# HB-power_v1_3.net
KiCad netlist of a schematic drawn in EAGLE
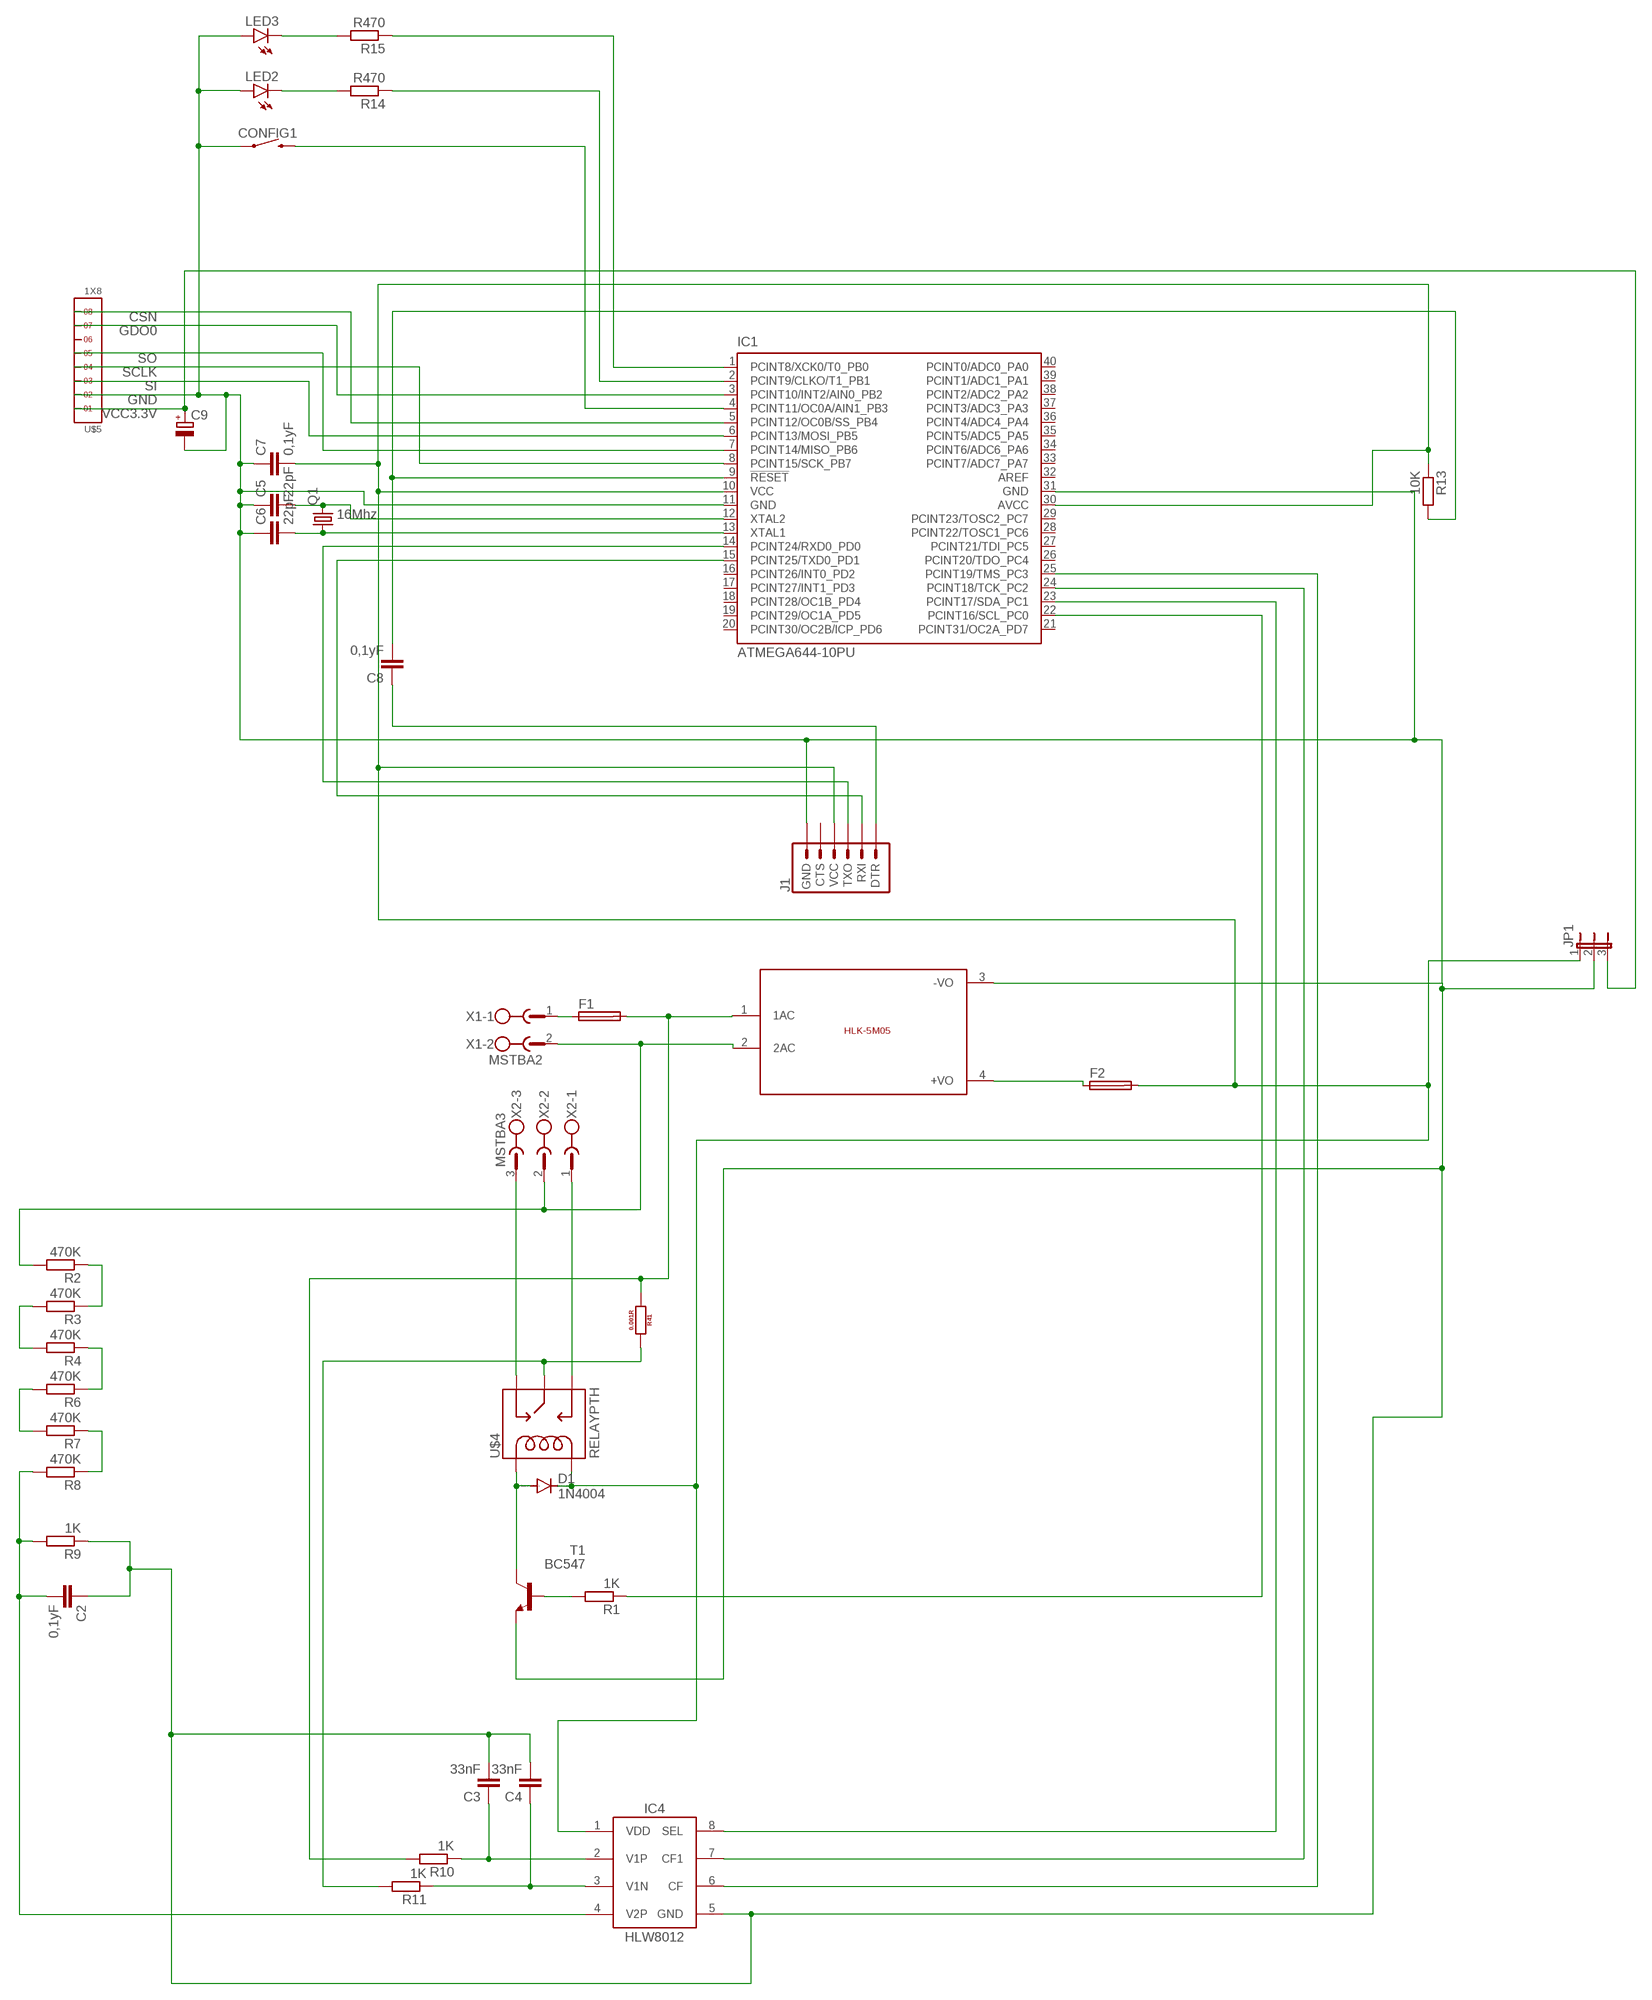
[diagram p0: schematic, sheet 1]

(export (version "E")
  (design (tool "Eeschema 10.0.6"))
  (components
    (comp (ref "C2")
      (value "0,1yF")
      (footprint "eagle-import:C050-024X044")
      (libsource (lib "eagle-import") (part "C-EU050-024X044"))
    )
    (comp (ref "C3")
      (value "33nF")
      (footprint "eagle-import:C050-024X044")
      (libsource (lib "eagle-import") (part "C-EU050-024X044"))
    )
    (comp (ref "C4")
      (value "33nF")
      (footprint "eagle-import:C050-024X044")
      (libsource (lib "eagle-import") (part "C-EU050-024X044"))
    )
    (comp (ref "C5")
      (value "22pF")
      (footprint "eagle-import:C025-024X044")
      (libsource (lib "eagle-import") (part "C-EU025-024X044"))
    )
    (comp (ref "C6")
      (value "22pF")
      (footprint "eagle-import:C025-024X044")
      (libsource (lib "eagle-import") (part "C-EU025-024X044"))
    )
    (comp (ref "C7")
      (value "0,1yF")
      (footprint "eagle-import:C025-024X044")
      (libsource (lib "eagle-import") (part "C-EU025-024X044"))
    )
    (comp (ref "C8")
      (value "0,1yF")
      (footprint "eagle-import:C025-024X044")
      (libsource (lib "eagle-import") (part "C-EU025-024X044"))
    )
    (comp (ref "C9")
      (value "CPOL-EUE2.5-5")
      (footprint "eagle-import:E2,5-5")
      (libsource (lib "eagle-import") (part "CPOL-EUE2.5-5"))
    )
    (comp (ref "CONFIG1")
      (value "MOMENTARY-SWITCH-SPST-PTH-6.0MM-KIT")
      (footprint "eagle-import:TACTILE_SWITCH_PTH_6.0MM_KIT")
      (libsource (lib "eagle-import") (part "MOMENTARY-SWITCH-SPST-PTH-6.0MM-KIT"))
    )
    (comp (ref "D1")
      (value "1N4004")
      (footprint "eagle-import:DO41-10")
      (libsource (lib "eagle-import") (part "1N4004"))
    )
    (comp (ref "F1")
      (value "SH22,5A")
      (footprint "eagle-import:SH22,5A")
      (fields (field (name "MPN") "0031.7701.11"))
      (libsource (lib "eagle-import") (part "SH22,5A"))
    )
    (comp (ref "F2")
      (value "SH22,5A")
      (footprint "eagle-import:SH22,5A")
      (fields (field (name "MPN") "0031.7701.11"))
      (libsource (lib "eagle-import") (part "SH22,5A"))
    )
    (comp (ref "IC1")
      (value "ATMEGA644-10PU")
      (footprint "eagle-import:DIL40")
      (fields (field (name "MPN") "ATMEGA644V-10PU"))
      (libsource (lib "eagle-import") (part "ATMEGA644-PU10"))
    )
    (comp (ref "IC4")
      (value "HLW8012")
      (footprint "eagle-import:SOP8")
      (libsource (lib "eagle-import") (part "HLW8012"))
    )
    (comp (ref "J1")
      (value "6_PIN_SERIAL_TARGETLONGPADS")
      (footprint "eagle-import:1X06_LONGPADS")
      (libsource (lib "eagle-import") (part "6_PIN_SERIAL_TARGETLONGPADS"))
    )
    (comp (ref "JP1")
      (value "JP2E")
      (footprint "eagle-import:JP2")
      (libsource (lib "eagle-import") (part "JP2E"))
    )
    (comp (ref "LED2")
      (value "LED3MM")
      (footprint "eagle-import:LED3MM")
      (libsource (lib "eagle-import") (part "LED3MM"))
    )
    (comp (ref "LED3")
      (value "LED3MM")
      (footprint "eagle-import:LED3MM")
      (libsource (lib "eagle-import") (part "LED3MM"))
    )
    (comp (ref "Q1")
      (value "16Mhz")
      (footprint "eagle-import:HC49U-V")
      (libsource (lib "eagle-import") (part "CRYSTALHC49U-V"))
    )
    (comp (ref "R1")
      (value "1K")
      (footprint "eagle-import:0309_10")
      (libsource (lib "eagle-import") (part "R-EU_0309/10"))
    )
    (comp (ref "R2")
      (value "470K")
      (footprint "eagle-import:0309_10")
      (libsource (lib "eagle-import") (part "R-EU_0309/10"))
    )
    (comp (ref "R3")
      (value "470K")
      (footprint "eagle-import:0309_10")
      (libsource (lib "eagle-import") (part "R-EU_0309/10"))
    )
    (comp (ref "R4")
      (value "470K")
      (footprint "eagle-import:0309_10")
      (libsource (lib "eagle-import") (part "R-EU_0309/10"))
    )
    (comp (ref "R6")
      (value "470K")
      (footprint "eagle-import:0309_10")
      (libsource (lib "eagle-import") (part "R-EU_0309/10"))
    )
    (comp (ref "R7")
      (value "470K")
      (footprint "eagle-import:0309_10")
      (libsource (lib "eagle-import") (part "R-EU_0309/10"))
    )
    (comp (ref "R8")
      (value "470K")
      (footprint "eagle-import:0309_10")
      (libsource (lib "eagle-import") (part "R-EU_0309/10"))
    )
    (comp (ref "R9")
      (value "1K")
      (footprint "eagle-import:0309_10")
      (libsource (lib "eagle-import") (part "R-EU_0309/10"))
    )
    (comp (ref "R10")
      (value "1K")
      (footprint "eagle-import:0309_10")
      (libsource (lib "eagle-import") (part "R-EU_0309/10"))
    )
    (comp (ref "R11")
      (value "1K")
      (footprint "eagle-import:0309_10")
      (libsource (lib "eagle-import") (part "R-EU_0309/10"))
    )
    (comp (ref "R13")
      (value "10K")
      (footprint "eagle-import:0309_10")
      (libsource (lib "eagle-import") (part "R-EU_0309/10"))
    )
    (comp (ref "R14")
      (value "R470")
      (footprint "eagle-import:0309_10")
      (libsource (lib "eagle-import") (part "R-EU_0309/10"))
    )
    (comp (ref "R15")
      (value "R470")
      (footprint "eagle-import:0309_10")
      (libsource (lib "eagle-import") (part "R-EU_0309/10"))
    )
    (comp (ref "R41")
      (value "0.001R")
      (footprint "eagle-import:2512")
      (libsource (lib "eagle-import") (part "RESISTOR2512"))
    )
    (comp (ref "T1")
      (value "BC547")
      (footprint "eagle-import:TO92")
      (libsource (lib "eagle-import") (part "BC547"))
    )
    (comp (ref "U$3")
      (value "5VDC/5W")
      (footprint "eagle-import:HLK-5M05")
      (libsource (lib "eagle-import") (part "HLK-5M05"))
    )
    (comp (ref "U$4")
      (value "RELAYPTH")
      (footprint "eagle-import:SRD-05VDC-SL-C")
      (libsource (lib "eagle-import") (part "RELAYPTH"))
    )
    (comp (ref "U$5")
      (value "1X8")
      (footprint "eagle-import:1X8")
      (libsource (lib "eagle-import") (part "1X8"))
    )
    (comp (ref "X1")
      (value "MSTBA2")
      (footprint "eagle-import:MSTBA2")
      (fields (field (name "MF") "FARNELL") (field (name "MPN") "1757242"))
      (libsource (lib "eagle-import") (part "MSTBA2"))
    )
    (comp (ref "X2")
      (value "MSTBA3")
      (footprint "eagle-import:MSTBA3")
      (fields (field (name "MF") "FARNELL") (field (name "MPN") "1757255"))
      (libsource (lib "eagle-import") (part "MSTBA3"))
    )
  )
  (nets
    (net (code "1") (name "/CSN") (class "Default")
      (node (ref "IC1") (pin "5") (pinfunction "PCINT12/OC0B/SS_PB4_5") (pintype "bidirectional"))
      (node (ref "U$5") (pin "8") (pinfunction "8_8") (pintype "bidirectional"))
    )
    (net (code "2") (name "/GDO0") (class "Default")
      (node (ref "IC1") (pin "3") (pinfunction "PCINT10/INT2/AIN0_PB2_3") (pintype "bidirectional"))
      (node (ref "U$5") (pin "7") (pinfunction "7_7") (pintype "bidirectional"))
    )
    (net (code "3") (name "/GND") (class "Default")
      (node (ref "C2") (pin "1") (pinfunction "1_1") (pintype "passive"))
      (node (ref "C3") (pin "2") (pinfunction "2_2") (pintype "passive"))
      (node (ref "C4") (pin "2") (pinfunction "2_2") (pintype "passive"))
      (node (ref "C5") (pin "1") (pinfunction "1_1") (pintype "passive"))
      (node (ref "C6") (pin "1") (pinfunction "1_1") (pintype "passive"))
      (node (ref "C7") (pin "1") (pinfunction "1_1") (pintype "passive"))
      (node (ref "C9") (pin "-") (pinfunction "-_-") (pintype "passive"))
      (node (ref "CONFIG1") (pin "1") (pinfunction "1_1") (pintype "passive"))
      (node (ref "IC1") (pin "11") (pinfunction "GND_11") (pintype "power_in"))
      (node (ref "IC1") (pin "31") (pinfunction "GND_31") (pintype "power_in"))
      (node (ref "IC4") (pin "5") (pinfunction "GND_5") (pintype "power_in"))
      (node (ref "J1") (pin "6") (pinfunction "GND_6") (pintype "passive"))
      (node (ref "JP1") (pin "2") (pinfunction "2_2") (pintype "passive"))
      (node (ref "LED2") (pin "A") (pinfunction "A_A") (pintype "passive"))
      (node (ref "LED3") (pin "A") (pinfunction "A_A") (pintype "passive"))
      (node (ref "R9") (pin "1") (pinfunction "1_1") (pintype "passive"))
      (node (ref "T1") (pin "1") (pinfunction "E_1") (pintype "passive"))
      (node (ref "U$3") (pin "3") (pinfunction "-VO_3") (pintype "bidirectional"))
      (node (ref "U$5") (pin "2") (pinfunction "2_2") (pintype "bidirectional"))
    )
    (net (code "4") (name "/SCLK") (class "Default")
      (node (ref "IC1") (pin "8") (pinfunction "PCINT15/SCK_PB7_8") (pintype "bidirectional"))
      (node (ref "U$5") (pin "4") (pinfunction "4_4") (pintype "bidirectional"))
    )
    (net (code "5") (name "/SI") (class "Default")
      (node (ref "IC1") (pin "6") (pinfunction "PCINT13/MOSI_PB5_6") (pintype "bidirectional"))
      (node (ref "U$5") (pin "3") (pinfunction "3_3") (pintype "bidirectional"))
    )
    (net (code "6") (name "/SO") (class "Default")
      (node (ref "IC1") (pin "7") (pinfunction "PCINT14/MISO_PB6_7") (pintype "bidirectional"))
      (node (ref "U$5") (pin "5") (pinfunction "5_5") (pintype "bidirectional"))
    )
    (net (code "7") (name "/VCC3.3V") (class "Default")
      (node (ref "C9") (pin "+") (pinfunction "+_+") (pintype "passive"))
      (node (ref "JP1") (pin "3") (pinfunction "3_3") (pintype "passive"))
      (node (ref "U$5") (pin "1") (pinfunction "1_1") (pintype "bidirectional"))
    )
    (net (code "8") (name "Net-(CONFIG1-2)") (class "Default")
      (node (ref "CONFIG1") (pin "3") (pinfunction "2_3") (pintype "passive"))
      (node (ref "IC1") (pin "4") (pinfunction "PCINT11/OC0A/AIN1_PB3_4") (pintype "bidirectional"))
    )
    (net (code "9") (name "Net-(F1-Pad1)") (class "Default")
      (node (ref "F1") (pin "1") (pinfunction "1_1") (pintype "passive"))
      (node (ref "X1") (pin "1") (pinfunction "1_1") (pintype "passive"))
    )
    (net (code "10") (name "Net-(IC1-AVCC)") (class "Default")
      (node (ref "C7") (pin "2") (pinfunction "2_2") (pintype "passive"))
      (node (ref "D1") (pin "C") (pinfunction "C_C") (pintype "passive"))
      (node (ref "F2") (pin "2") (pinfunction "2_2") (pintype "passive"))
      (node (ref "IC1") (pin "10") (pinfunction "VCC_10") (pintype "power_in"))
      (node (ref "IC1") (pin "30") (pinfunction "AVCC_30") (pintype "power_in"))
      (node (ref "IC4") (pin "1") (pinfunction "VDD_1") (pintype "power_in"))
      (node (ref "J1") (pin "4") (pinfunction "VCC_4") (pintype "passive"))
      (node (ref "JP1") (pin "1") (pinfunction "1_1") (pintype "passive"))
      (node (ref "R13") (pin "1") (pinfunction "1_1") (pintype "passive"))
      (node (ref "U$4") (pin "COIL0") (pinfunction "COIL0_COIL0") (pintype "bidirectional"))
    )
    (net (code "11") (name "Net-(IC1-PCINT8{slash}XCK0{slash}T0_PB0)") (class "Default")
      (node (ref "IC1") (pin "1") (pinfunction "PCINT8/XCK0/T0_PB0_1") (pintype "bidirectional"))
      (node (ref "R15") (pin "1") (pinfunction "1_1") (pintype "passive"))
    )
    (net (code "12") (name "Net-(IC1-PCINT9{slash}CLKO{slash}T1_PB1)") (class "Default")
      (node (ref "IC1") (pin "2") (pinfunction "PCINT9/CLKO/T1_PB1_2") (pintype "bidirectional"))
      (node (ref "R14") (pin "1") (pinfunction "1_1") (pintype "passive"))
    )
    (net (code "13") (name "Net-(IC1-PCINT16{slash}SCL_PC0)") (class "Default")
      (node (ref "IC1") (pin "22") (pinfunction "PCINT16/SCL_PC0_22") (pintype "bidirectional"))
      (node (ref "R1") (pin "1") (pinfunction "1_1") (pintype "passive"))
    )
    (net (code "14") (name "Net-(IC1-PCINT17{slash}SDA_PC1)") (class "Default")
      (node (ref "IC1") (pin "23") (pinfunction "PCINT17/SDA_PC1_23") (pintype "bidirectional"))
      (node (ref "IC4") (pin "8") (pinfunction "SEL_8") (pintype "input"))
    )
    (net (code "15") (name "Net-(IC1-PCINT18{slash}TCK_PC2)") (class "Default")
      (node (ref "IC1") (pin "24") (pinfunction "PCINT18/TCK_PC2_24") (pintype "bidirectional"))
      (node (ref "IC4") (pin "7") (pinfunction "CF1_7") (pintype "output"))
    )
    (net (code "16") (name "Net-(IC1-PCINT19{slash}TMS_PC3)") (class "Default")
      (node (ref "IC1") (pin "25") (pinfunction "PCINT19/TMS_PC3_25") (pintype "bidirectional"))
      (node (ref "IC4") (pin "6") (pinfunction "CF_6") (pintype "output"))
    )
    (net (code "17") (name "Net-(IC1-PCINT24{slash}RXD0_PD0)") (class "Default")
      (node (ref "IC1") (pin "14") (pinfunction "PCINT24/RXD0_PD0_14") (pintype "bidirectional"))
      (node (ref "J1") (pin "3") (pinfunction "TXO_3") (pintype "passive"))
    )
    (net (code "18") (name "Net-(IC1-PCINT25{slash}TXD0_PD1)") (class "Default")
      (node (ref "IC1") (pin "15") (pinfunction "PCINT25/TXD0_PD1_15") (pintype "bidirectional"))
      (node (ref "J1") (pin "2") (pinfunction "RXI_2") (pintype "passive"))
    )
    (net (code "19") (name "Net-(IC1-XTAL1)") (class "Default")
      (node (ref "C6") (pin "2") (pinfunction "2_2") (pintype "passive"))
      (node (ref "IC1") (pin "13") (pinfunction "XTAL1_13") (pintype "input"))
      (node (ref "Q1") (pin "1") (pinfunction "1_1") (pintype "passive"))
    )
    (net (code "20") (name "Net-(IC1-XTAL2)") (class "Default")
      (node (ref "C5") (pin "2") (pinfunction "2_2") (pintype "passive"))
      (node (ref "IC1") (pin "12") (pinfunction "XTAL2_12") (pintype "output"))
      (node (ref "Q1") (pin "2") (pinfunction "2_2") (pintype "passive"))
    )
    (net (code "21") (name "Net-(IC1-~{RESET})") (class "Default")
      (node (ref "C8") (pin "2") (pinfunction "2_2") (pintype "passive"))
      (node (ref "IC1") (pin "9") (pinfunction "~{RESET}_9") (pintype "input"))
      (node (ref "R13") (pin "2") (pinfunction "2_2") (pintype "passive"))
    )
    (net (code "22") (name "Net-(IC4-V1N)") (class "Default")
      (node (ref "C4") (pin "1") (pinfunction "1_1") (pintype "passive"))
      (node (ref "IC4") (pin "3") (pinfunction "V1N_3") (pintype "input"))
      (node (ref "R11") (pin "1") (pinfunction "1_1") (pintype "passive"))
    )
    (net (code "23") (name "Net-(IC4-V1P)") (class "Default")
      (node (ref "C3") (pin "1") (pinfunction "1_1") (pintype "passive"))
      (node (ref "IC4") (pin "2") (pinfunction "V1P_2") (pintype "input"))
      (node (ref "R10") (pin "1") (pinfunction "1_1") (pintype "passive"))
    )
    (net (code "24") (name "Net-(IC4-V2P)") (class "Default")
      (node (ref "C2") (pin "2") (pinfunction "2_2") (pintype "passive"))
      (node (ref "IC4") (pin "4") (pinfunction "V2P_4") (pintype "input"))
      (node (ref "R8") (pin "2") (pinfunction "2_2") (pintype "passive"))
      (node (ref "R9") (pin "2") (pinfunction "2_2") (pintype "passive"))
    )
    (net (code "25") (name "Net-(J1-DTR)") (class "Default")
      (node (ref "C8") (pin "1") (pinfunction "1_1") (pintype "passive"))
      (node (ref "J1") (pin "1") (pinfunction "DTR_1") (pintype "passive"))
    )
    (net (code "26") (name "Net-(LED2-C)") (class "Default")
      (node (ref "LED2") (pin "K") (pinfunction "C_K") (pintype "passive"))
      (node (ref "R14") (pin "2") (pinfunction "2_2") (pintype "passive"))
    )
    (net (code "27") (name "Net-(LED3-C)") (class "Default")
      (node (ref "LED3") (pin "K") (pinfunction "C_K") (pintype "passive"))
      (node (ref "R15") (pin "2") (pinfunction "2_2") (pintype "passive"))
    )
    (net (code "28") (name "Net-(R2-Pad1)") (class "Default")
      (node (ref "R2") (pin "1") (pinfunction "1_1") (pintype "passive"))
      (node (ref "R3") (pin "1") (pinfunction "1_1") (pintype "passive"))
    )
    (net (code "29") (name "Net-(R3-Pad2)") (class "Default")
      (node (ref "R3") (pin "2") (pinfunction "2_2") (pintype "passive"))
      (node (ref "R4") (pin "2") (pinfunction "2_2") (pintype "passive"))
    )
    (net (code "30") (name "Net-(R4-Pad1)") (class "Default")
      (node (ref "R4") (pin "1") (pinfunction "1_1") (pintype "passive"))
      (node (ref "R6") (pin "1") (pinfunction "1_1") (pintype "passive"))
    )
    (net (code "31") (name "Net-(R6-Pad2)") (class "Default")
      (node (ref "R6") (pin "2") (pinfunction "2_2") (pintype "passive"))
      (node (ref "R7") (pin "2") (pinfunction "2_2") (pintype "passive"))
    )
    (net (code "32") (name "Net-(R7-Pad1)") (class "Default")
      (node (ref "R7") (pin "1") (pinfunction "1_1") (pintype "passive"))
      (node (ref "R8") (pin "1") (pinfunction "1_1") (pintype "passive"))
    )
    (net (code "33") (name "Net-(R11-Pad2)") (class "Default")
      (node (ref "R11") (pin "2") (pinfunction "2_2") (pintype "passive"))
      (node (ref "R41") (pin "2") (pinfunction "2_2") (pintype "passive"))
      (node (ref "U$4") (pin "SWCOMMON") (pinfunction "SWCOMMON_SWCOMMON") (pintype "bidirectional"))
    )
    (net (code "34") (name "Net-(T1-B)") (class "Default")
      (node (ref "R1") (pin "2") (pinfunction "2_2") (pintype "passive"))
      (node (ref "T1") (pin "2") (pinfunction "B_2") (pintype "passive"))
    )
    (net (code "35") (name "Net-(T1-C)") (class "Default")
      (node (ref "D1") (pin "A") (pinfunction "A_A") (pintype "passive"))
      (node (ref "T1") (pin "3") (pinfunction "C_3") (pintype "passive"))
      (node (ref "U$4") (pin "COIL1") (pinfunction "COIL1_COIL1") (pintype "bidirectional"))
    )
    (net (code "36") (name "Net-(U$3-+VO)") (class "Default")
      (node (ref "F2") (pin "1") (pinfunction "1_1") (pintype "passive"))
      (node (ref "U$3") (pin "4") (pinfunction "+VO_4") (pintype "bidirectional"))
    )
    (net (code "37") (name "Net-(U$3-1AC)") (class "Default")
      (node (ref "F1") (pin "2") (pinfunction "2_2") (pintype "passive"))
      (node (ref "R10") (pin "2") (pinfunction "2_2") (pintype "passive"))
      (node (ref "R41") (pin "1") (pinfunction "1_1") (pintype "passive"))
      (node (ref "U$3") (pin "1") (pinfunction "1AC_1") (pintype "bidirectional"))
    )
    (net (code "38") (name "Net-(U$3-2AC)") (class "Default")
      (node (ref "R2") (pin "2") (pinfunction "2_2") (pintype "passive"))
      (node (ref "U$3") (pin "2") (pinfunction "2AC_2") (pintype "bidirectional"))
      (node (ref "X1") (pin "2") (pinfunction "1_2") (pintype "passive"))
      (node (ref "X2") (pin "2") (pinfunction "1_2") (pintype "passive"))
    )
    (net (code "39") (name "Net-(U$4-PadSWOPEN)") (class "Default")
      (node (ref "U$4") (pin "SWOPEN") (pinfunction "SWOPEN_SWOPEN") (pintype "bidirectional"))
      (node (ref "X2") (pin "1") (pinfunction "1_1") (pintype "passive"))
    )
    (net (code "40") (name "Net-(U$4-SWCLOSE)") (class "Default")
      (node (ref "U$4") (pin "SWCLOSED") (pinfunction "SWCLOSE_SWCLOSED") (pintype "bidirectional"))
      (node (ref "X2") (pin "3") (pinfunction "1_3") (pintype "passive"))
    )
    (net (code "41") (name "unconnected-(IC1-AREF-Pad32)") (class "Default")
      (node (ref "IC1") (pin "32") (pinfunction "AREF_32") (pintype "passive"))
    )
    (net (code "42") (name "unconnected-(IC1-PCINT0{slash}ADC0_PA0-Pad40)") (class "Default")
      (node (ref "IC1") (pin "40") (pinfunction "PCINT0/ADC0_PA0_40") (pintype "bidirectional"))
    )
    (net (code "43") (name "unconnected-(IC1-PCINT1{slash}ADC1_PA1-Pad39)") (class "Default")
      (node (ref "IC1") (pin "39") (pinfunction "PCINT1/ADC1_PA1_39") (pintype "bidirectional"))
    )
    (net (code "44") (name "unconnected-(IC1-PCINT2{slash}ADC2_PA2-Pad38)") (class "Default")
      (node (ref "IC1") (pin "38") (pinfunction "PCINT2/ADC2_PA2_38") (pintype "bidirectional"))
    )
    (net (code "45") (name "unconnected-(IC1-PCINT3{slash}ADC3_PA3-Pad37)") (class "Default")
      (node (ref "IC1") (pin "37") (pinfunction "PCINT3/ADC3_PA3_37") (pintype "bidirectional"))
    )
    (net (code "46") (name "unconnected-(IC1-PCINT4{slash}ADC4_PA4-Pad36)") (class "Default")
      (node (ref "IC1") (pin "36") (pinfunction "PCINT4/ADC4_PA4_36") (pintype "bidirectional"))
    )
    (net (code "47") (name "unconnected-(IC1-PCINT5{slash}ADC5_PA5-Pad35)") (class "Default")
      (node (ref "IC1") (pin "35") (pinfunction "PCINT5/ADC5_PA5_35") (pintype "bidirectional"))
    )
    (net (code "48") (name "unconnected-(IC1-PCINT6{slash}ADC6_PA6-Pad34)") (class "Default")
      (node (ref "IC1") (pin "34") (pinfunction "PCINT6/ADC6_PA6_34") (pintype "bidirectional"))
    )
    (net (code "49") (name "unconnected-(IC1-PCINT7{slash}ADC7_PA7-Pad33)") (class "Default")
      (node (ref "IC1") (pin "33") (pinfunction "PCINT7/ADC7_PA7_33") (pintype "bidirectional"))
    )
    (net (code "50") (name "unconnected-(IC1-PCINT20{slash}TDO_PC4-Pad26)") (class "Default")
      (node (ref "IC1") (pin "26") (pinfunction "PCINT20/TDO_PC4_26") (pintype "bidirectional"))
    )
    (net (code "51") (name "unconnected-(IC1-PCINT21{slash}TDI_PC5-Pad27)") (class "Default")
      (node (ref "IC1") (pin "27") (pinfunction "PCINT21/TDI_PC5_27") (pintype "bidirectional"))
    )
    (net (code "52") (name "unconnected-(IC1-PCINT22{slash}TOSC1_PC6-Pad28)") (class "Default")
      (node (ref "IC1") (pin "28") (pinfunction "PCINT22/TOSC1_PC6_28") (pintype "bidirectional"))
    )
    (net (code "53") (name "unconnected-(IC1-PCINT23{slash}TOSC2_PC7-Pad29)") (class "Default")
      (node (ref "IC1") (pin "29") (pinfunction "PCINT23/TOSC2_PC7_29") (pintype "bidirectional"))
    )
    (net (code "54") (name "unconnected-(IC1-PCINT26{slash}INT0_PD2-Pad16)") (class "Default")
      (node (ref "IC1") (pin "16") (pinfunction "PCINT26/INT0_PD2_16") (pintype "bidirectional"))
    )
    (net (code "55") (name "unconnected-(IC1-PCINT27{slash}INT1_PD3-Pad17)") (class "Default")
      (node (ref "IC1") (pin "17") (pinfunction "PCINT27/INT1_PD3_17") (pintype "bidirectional"))
    )
    (net (code "56") (name "unconnected-(IC1-PCINT28{slash}OC1B_PD4-Pad18)") (class "Default")
      (node (ref "IC1") (pin "18") (pinfunction "PCINT28/OC1B_PD4_18") (pintype "bidirectional"))
    )
    (net (code "57") (name "unconnected-(IC1-PCINT29{slash}OC1A_PD5-Pad19)") (class "Default")
      (node (ref "IC1") (pin "19") (pinfunction "PCINT29/OC1A_PD5_19") (pintype "bidirectional"))
    )
    (net (code "58") (name "unconnected-(IC1-PCINT30{slash}OC2B{slash}ICP_PD6-Pad20)") (class "Default")
      (node (ref "IC1") (pin "20") (pinfunction "PCINT30/OC2B/ICP_PD6_20") (pintype "bidirectional"))
    )
    (net (code "59") (name "unconnected-(IC1-PCINT31{slash}OC2A_PD7-Pad21)") (class "Default")
      (node (ref "IC1") (pin "21") (pinfunction "PCINT31/OC2A_PD7_21") (pintype "bidirectional"))
    )
    (net (code "60") (name "unconnected-(J1-CTS-Pad5)") (class "Default")
      (node (ref "J1") (pin "5") (pinfunction "CTS_5") (pintype "passive"))
    )
    (net (code "61") (name "unconnected-(U$5-Pad6)") (class "Default")
      (node (ref "U$5") (pin "6") (pinfunction "6_6") (pintype "bidirectional"))
    )
  )
)
